# power_supply5v.net
KiCad netlist of a schematic drawn in EAGLE
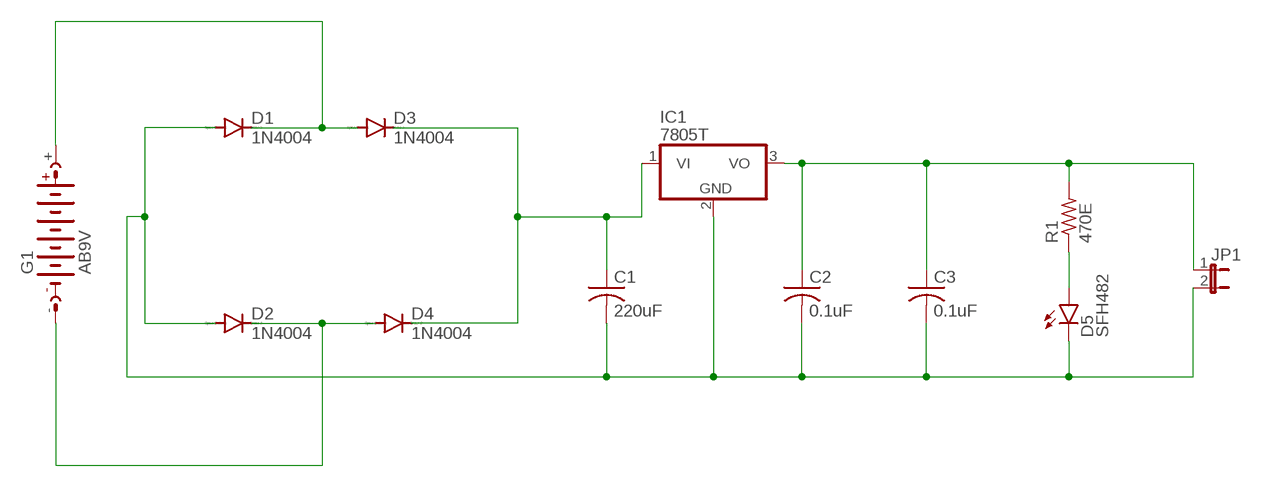
[diagram p0: schematic, sheet 1]

(export (version "E")
  (design (tool "Eeschema 10.0.6"))
  (components
    (comp (ref "C1")
      (value "220uF")
      (footprint "eagle-import:C050-024X044")
      (libsource (lib "eagle-import") (part "C-US050-024X044"))
    )
    (comp (ref "C2")
      (value "0.1uF")
      (footprint "eagle-import:C050-024X044")
      (libsource (lib "eagle-import") (part "C-US050-024X044"))
    )
    (comp (ref "C3")
      (value "0.1uF")
      (footprint "eagle-import:C050-024X044")
      (libsource (lib "eagle-import") (part "C-US050-024X044"))
    )
    (comp (ref "D1")
      (value "1N4004")
      (footprint "eagle-import:DO41-10")
      (libsource (lib "eagle-import") (part "1N4004"))
    )
    (comp (ref "D2")
      (value "1N4004")
      (footprint "eagle-import:DO41-10")
      (libsource (lib "eagle-import") (part "1N4004"))
    )
    (comp (ref "D3")
      (value "1N4004")
      (footprint "eagle-import:DO41-10")
      (libsource (lib "eagle-import") (part "1N4004"))
    )
    (comp (ref "D4")
      (value "1N4004")
      (footprint "eagle-import:DO41-10")
      (libsource (lib "eagle-import") (part "1N4004"))
    )
    (comp (ref "D5")
      (value "SFH482")
      (footprint "eagle-import:SFH482")
      (libsource (lib "eagle-import") (part "SFH482"))
    )
    (comp (ref "G1")
      (value "AB9V")
      (footprint "eagle-import:AB9V")
      (libsource (lib "eagle-import") (part "AB9V"))
    )
    (comp (ref "IC1")
      (value "7805T")
      (footprint "eagle-import:TO220H")
      (libsource (lib "eagle-import") (part "78T05"))
    )
    (comp (ref "JP1")
      (value "JP1E")
      (footprint "eagle-import:JP1")
      (libsource (lib "eagle-import") (part "JP1E"))
    )
    (comp (ref "R1")
      (value "470E")
      (footprint "eagle-import:0204_7")
      (libsource (lib "eagle-import") (part "R-US_0204/7"))
    )
  )
  (nets
    (net (code "1") (name "Net-(D1-PadC)") (class "Default")
      (node (ref "D1") (pin "C") (pinfunction "C_C") (pintype "passive"))
      (node (ref "D3") (pin "A") (pinfunction "A_A") (pintype "passive"))
      (node (ref "G1") (pin "+") (pinfunction "+_+") (pintype "passive"))
    )
    (net (code "2") (name "Net-(D2-PadC)") (class "Default")
      (node (ref "D2") (pin "C") (pinfunction "C_C") (pintype "passive"))
      (node (ref "D4") (pin "A") (pinfunction "A_A") (pintype "passive"))
      (node (ref "G1") (pin "-") (pinfunction "-_-") (pintype "passive"))
    )
    (net (code "3") (name "Net-(D5-C)") (class "Default")
      (node (ref "C1") (pin "2") (pinfunction "2_2") (pintype "passive"))
      (node (ref "C2") (pin "2") (pinfunction "2_2") (pintype "passive"))
      (node (ref "C3") (pin "2") (pinfunction "2_2") (pintype "passive"))
      (node (ref "D1") (pin "A") (pinfunction "A_A") (pintype "passive"))
      (node (ref "D2") (pin "A") (pinfunction "A_A") (pintype "passive"))
      (node (ref "D5") (pin "K") (pinfunction "C_K") (pintype "passive"))
      (node (ref "IC1") (pin "2") (pinfunction "GND_2") (pintype "passive"))
      (node (ref "JP1") (pin "2") (pinfunction "2_2") (pintype "passive"))
    )
    (net (code "4") (name "Net-(D5-PadA)") (class "Default")
      (node (ref "D5") (pin "A") (pinfunction "A_A") (pintype "passive"))
      (node (ref "R1") (pin "1") (pinfunction "1_1") (pintype "passive"))
    )
    (net (code "5") (name "Net-(IC1-VI)") (class "Default")
      (node (ref "C1") (pin "1") (pinfunction "1_1") (pintype "passive"))
      (node (ref "D3") (pin "C") (pinfunction "C_C") (pintype "passive"))
      (node (ref "D4") (pin "C") (pinfunction "C_C") (pintype "passive"))
      (node (ref "IC1") (pin "1") (pinfunction "VI_1") (pintype "input"))
    )
    (net (code "6") (name "Net-(IC1-VO)") (class "Default")
      (node (ref "C2") (pin "1") (pinfunction "1_1") (pintype "passive"))
      (node (ref "C3") (pin "1") (pinfunction "1_1") (pintype "passive"))
      (node (ref "IC1") (pin "3") (pinfunction "VO_3") (pintype "passive"))
      (node (ref "JP1") (pin "1") (pinfunction "1_1") (pintype "passive"))
      (node (ref "R1") (pin "2") (pinfunction "2_2") (pintype "passive"))
    )
  )
)
